# SCH_main.net
KiCad netlist of a schematic drawn in Altium Designer
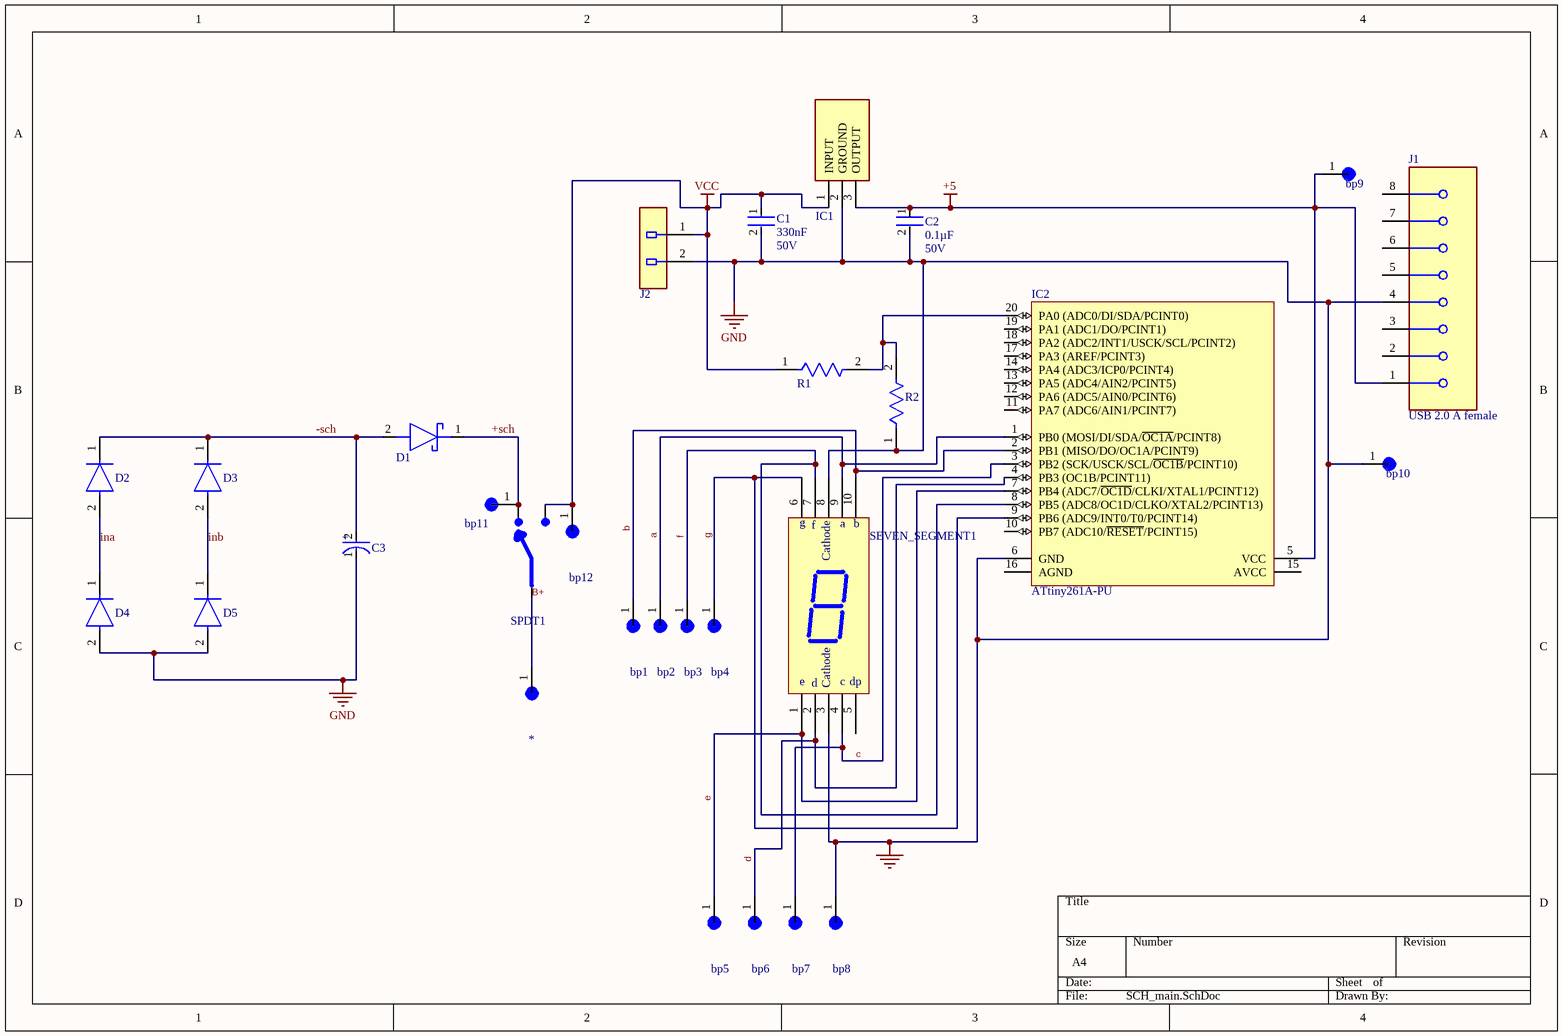
[diagram p0: SCH_main.SchDoc]

(export (version "E")
  (design (tool "Eeschema 10.0.6"))
  (components
    (comp (ref "*")
      (value "Battery Pad")
      (footprint "Battery pad")
      (libsource (lib "Schlib1") (part "Battery Pad"))
    )
    (comp (ref "bp1")
      (value "Battery Pad")
      (footprint "Battery pad")
      (libsource (lib "Schlib1") (part "Battery Pad"))
    )
    (comp (ref "bp2")
      (value "Battery Pad")
      (footprint "Battery pad")
      (libsource (lib "Schlib1") (part "Battery Pad"))
    )
    (comp (ref "bp3")
      (value "Battery Pad")
      (footprint "Battery pad")
      (libsource (lib "Schlib1") (part "Battery Pad"))
    )
    (comp (ref "bp4")
      (value "Battery Pad")
      (footprint "Battery pad")
      (libsource (lib "Schlib1") (part "Battery Pad"))
    )
    (comp (ref "bp5")
      (value "Battery Pad")
      (footprint "Battery pad")
      (libsource (lib "Schlib1") (part "Battery Pad"))
    )
    (comp (ref "bp6")
      (value "Battery Pad")
      (footprint "Battery pad")
      (libsource (lib "Schlib1") (part "Battery Pad"))
    )
    (comp (ref "bp7")
      (value "Battery Pad")
      (footprint "Battery pad")
      (libsource (lib "Schlib1") (part "Battery Pad"))
    )
    (comp (ref "bp8")
      (value "Battery Pad")
      (footprint "Battery pad")
      (libsource (lib "Schlib1") (part "Battery Pad"))
    )
    (comp (ref "bp9")
      (value "Battery Pad")
      (footprint "Battery pad")
      (libsource (lib "Schlib1") (part "Battery Pad"))
    )
    (comp (ref "bp10")
      (value "Battery Pad")
      (footprint "Battery pad")
      (libsource (lib "Schlib1") (part "Battery Pad"))
    )
    (comp (ref "bp11")
      (value "Battery Pad")
      (footprint "Battery pad")
      (libsource (lib "Schlib1") (part "Battery Pad"))
    )
    (comp (ref "bp12")
      (value "Battery Pad")
      (footprint "Battery pad")
      (libsource (lib "Schlib1") (part "Battery Pad"))
    )
    (comp (ref "C1")
      (value "Cap_Kemet_C322C334M5U5TA7301_eec")
      (footprint "Kemet_C322C334M5U5TA7301_0")
      (description "CAP CER 0.33UF 50V Z5U RADIAL")
      (fields
        (field (name "PART NUMBER") "C322C334M5U5TA7301")
        (field (name "MANUFACTURER") "Kemet")
        (field (name "CAPACITANCE") "330nF")
        (field (name "VOLTAGE") "50V")
      )
      (libsource (lib "Integrated_Library1") (part "Cap_Kemet_C322C334M5U5TA7301_eec"))
    )
    (comp (ref "C2")
      (value "Cap_BC_Components_K104Z15Y5VF5TL2_eec")
      (footprint "BC_Components_K104Z15Y5VF5TL2_0")
      (description "CAP CER 0.1UF 50V Y5V RADIAL")
      (fields
        (field (name "MANUFACTURER") "BC Components")
        (field (name "MOUSER PART NUMBER") "594-K104Z15Y5VF5TL2")
        (field (name "CAPACITANCE") "0.1µF")
        (field (name "VOLTAGE") "50V")
      )
      (libsource (lib "Integrated_Library1") (part "Cap_BC_Components_K104Z15Y5VF5TL2_eec"))
    )
    (comp (ref "C3")
      (value "ECA-1CM471")
      (footprint "Panasonic_ECA-1_0")
      (libsource (lib "Schlib1") (part "ECA-1CM471"))
    )
    (comp (ref "D1")
      (value "SD103A-TR")
      (footprint "DIOAD950W60L350D150")
      (description "Schottky Diode")
      (fields (field (name "MOUSER PART NUMBER") "625-SD103A"))
      (libsource (lib "Schlib1") (part "SD103A-TR"))
    )
    (comp (ref "D2")
      (value "Diode_Vishay_1N4007-E3-73_eec")
      (footprint "Vishay_1N4007-E3-73_0")
      (description "DIODE GEN PURP 1KV 1A DO204AL")
      (fields (field (name "PART NUMBER") "1N4007-E3/73") (field (name "MANUFACTURER") "Vishay"))
      (libsource (lib "Integrated_Library1") (part "Diode_Vishay_1N4007-E3-73_eec"))
    )
    (comp (ref "D3")
      (value "Diode_Vishay_1N4007-E3-73_eec")
      (footprint "Vishay_1N4007-E3-73_0")
      (description "DIODE GEN PURP 1KV 1A DO204AL")
      (fields (field (name "PART NUMBER") "1N4007-E3/73") (field (name "MANUFACTURER") "Vishay"))
      (libsource (lib "Integrated_Library1") (part "Diode_Vishay_1N4007-E3-73_eec"))
    )
    (comp (ref "D4")
      (value "Diode_Vishay_1N4007-E3-73_eec")
      (footprint "Vishay_1N4007-E3-73_0")
      (description "DIODE GEN PURP 1KV 1A DO204AL")
      (fields (field (name "PART NUMBER") "1N4007-E3/73") (field (name "MANUFACTURER") "Vishay"))
      (libsource (lib "Integrated_Library1") (part "Diode_Vishay_1N4007-E3-73_eec"))
    )
    (comp (ref "D5")
      (value "Diode_Vishay_1N4007-E3-73_eec")
      (footprint "Vishay_1N4007-E3-73_0")
      (description "DIODE GEN PURP 1KV 1A DO204AL")
      (fields (field (name "PART NUMBER") "1N4007-E3/73") (field (name "MANUFACTURER") "Vishay"))
      (libsource (lib "Integrated_Library1") (part "Diode_Vishay_1N4007-E3-73_eec"))
    )
    (comp (ref "IC1")
      (value "LM7805CT")
      (footprint "TO254P470X1016X2019-3P")
      (description "Integrated Circuit")
      (fields (field (name "MOUSER PART NUMBER") "926-LM7805CT"))
      (libsource (lib "Schlib1") (part "LM7805CT"))
    )
    (comp (ref "IC2")
      (value "ATtiny261A-PU")
      (footprint "20P3")
      (fields (field (name "PARTNUMBER") "ATTINY261A-PU"))
      (libsource (lib "Schlib1") (part "ATTINY261A-PU"))
    )
    (comp (ref "J1")
      (value "USB 2.0 A female")
      (footprint "usbA2F_Molex_67329-8000_0")
      (libsource (lib "Schlib1") (part "67329-8000"))
    )
    (comp (ref "J2")
      (value "826926-2")
      (footprint "TE_826926-2_0")
      (libsource (lib "Integrated_Library1") (part "826926-2"))
    )
    (comp (ref "R1")
      (value "CFR25J100R")
      (footprint "RESISTOR_Tyco_CFR25J100R_0")
      (description "Carbon Film Resistors - Through Hole 100Ohm 1/3W 1200PPM")
      (fields (field (name "MANUFACTURER") "TE Connectivity") (field (name "TOLERANCE") "5%"))
      (libsource (lib "Schlib1") (part "CFR25J100R"))
    )
    (comp (ref "R2")
      (value "CFR25J100R")
      (footprint "RESISTOR_Tyco_CFR25J100R_0")
      (description "Carbon Film Resistors - Through Hole 100Ohm 1/3W 1200PPM")
      (fields (field (name "MANUFACTURER") "TE Connectivity") (field (name "TOLERANCE") "5%"))
      (libsource (lib "Schlib1") (part "CFR25J100R"))
    )
    (comp (ref "SEVEN_SEGMENT1")
      (value "CC_SEVEN_SEGMENT")
      (footprint "7SEG-Avago-Broadcam_HDSP-5551_0")
      (libsource (lib "Schlib1") (part "CC_SEVEN_SEGMENT"))
    )
    (comp (ref "SPDT1")
      (value "spdt_JS202011SCQN")
      (description "C & K COMPONENTS - JS202011SCQN - SWITCH, DPDT, 0.6A, 6VDC, SMD")
      (fields (field (name "MANUFACTURER") "ITT C&K"))
      (libsource (lib "Schlib1") (part "spdt_JS202011SCQN"))
    )
  )
  (nets
    (net (code "1") (name "+5") (class "Default")
      (node (ref "C2") (pin "1") (pinfunction "1_1") (pintype "passive"))
      (node (ref "IC1") (pin "3") (pinfunction "OUTPUT_3") (pintype "passive"))
      (node (ref "IC2") (pin "5") (pinfunction "VCC_5") (pintype "power_in"))
      (node (ref "J1") (pin "1") (pinfunction "1_1") (pintype "passive"))
      (node (ref "bp9") (pin "1") (pinfunction "1_1") (pintype "passive"))
    )
    (net (code "2") (name "/+sch") (class "Default")
      (node (ref "D1") (pin "1") (pinfunction "K_1") (pintype "passive"))
      (node (ref "SPDT1") (pin "2") (pinfunction "2_2") (pintype "passive"))
      (node (ref "bp11") (pin "1") (pinfunction "1_1") (pintype "passive"))
    )
    (net (code "3") (name "/-sch") (class "Default")
      (node (ref "C3") (pin "2") (pinfunction "+_2") (pintype "passive"))
      (node (ref "D1") (pin "2") (pinfunction "A_2") (pintype "passive"))
      (node (ref "D2") (pin "1") (pinfunction "C_1") (pintype "passive"))
      (node (ref "D3") (pin "1") (pinfunction "C_1") (pintype "passive"))
    )
    (net (code "4") (name "/B+") (class "Default")
      (node (ref "*") (pin "1") (pinfunction "1_1") (pintype "passive"))
    )
    (net (code "5") (name "/a") (class "Default")
      (node (ref "IC2") (pin "1") (pinfunction "PB0_(MOSI/DI/SDA/~{OC1A}/PCINT8)_1") (pintype "bidirectional"))
      (node (ref "SEVEN_SEGMENT1") (pin "9") (pinfunction "9_9") (pintype "passive"))
      (node (ref "bp2") (pin "1") (pinfunction "1_1") (pintype "passive"))
    )
    (net (code "6") (name "/b") (class "Default")
      (node (ref "IC2") (pin "2") (pinfunction "PB1_(MISO/DO/OC1A/PCINT9)_2") (pintype "bidirectional"))
      (node (ref "SEVEN_SEGMENT1") (pin "10") (pinfunction "10_10") (pintype "passive"))
      (node (ref "bp1") (pin "1") (pinfunction "1_1") (pintype "passive"))
    )
    (net (code "7") (name "/c") (class "Default")
      (node (ref "IC2") (pin "3") (pinfunction "PB2_(SCK/USCK/SCL/~{OC1B}/PCINT10)_3") (pintype "bidirectional"))
      (node (ref "SEVEN_SEGMENT1") (pin "4") (pinfunction "4_4") (pintype "passive"))
      (node (ref "bp7") (pin "1") (pinfunction "1_1") (pintype "passive"))
    )
    (net (code "8") (name "/d") (class "Default")
      (node (ref "IC2") (pin "4") (pinfunction "PB3_(OC1B/PCINT11)_4") (pintype "bidirectional"))
      (node (ref "SEVEN_SEGMENT1") (pin "2") (pinfunction "2_2") (pintype "passive"))
      (node (ref "bp6") (pin "1") (pinfunction "1_1") (pintype "passive"))
    )
    (net (code "9") (name "/e") (class "Default")
      (node (ref "IC2") (pin "7") (pinfunction "PB4_(ADC7/~{OC1D}/CLKI/XTAL1/PCINT12)_7") (pintype "bidirectional"))
      (node (ref "SEVEN_SEGMENT1") (pin "1") (pinfunction "1_1") (pintype "passive"))
      (node (ref "bp5") (pin "1") (pinfunction "1_1") (pintype "passive"))
    )
    (net (code "10") (name "/f") (class "Default")
      (node (ref "IC2") (pin "8") (pinfunction "PB5_(ADC8/OC1D/CLKO/XTAL2/PCINT13)_8") (pintype "bidirectional"))
      (node (ref "SEVEN_SEGMENT1") (pin "7") (pinfunction "7_7") (pintype "passive"))
      (node (ref "bp3") (pin "1") (pinfunction "1_1") (pintype "passive"))
    )
    (net (code "11") (name "/g") (class "Default")
      (node (ref "IC2") (pin "9") (pinfunction "PB6_(ADC9/INT0/T0/PCINT14)_9") (pintype "bidirectional"))
      (node (ref "SEVEN_SEGMENT1") (pin "6") (pinfunction "6_6") (pintype "passive"))
      (node (ref "bp4") (pin "1") (pinfunction "1_1") (pintype "passive"))
    )
    (net (code "12") (name "/ina") (class "Default")
      (node (ref "D2") (pin "2") (pinfunction "A_2") (pintype "passive"))
      (node (ref "D4") (pin "1") (pinfunction "C_1") (pintype "passive"))
    )
    (net (code "13") (name "/inb") (class "Default")
      (node (ref "D3") (pin "2") (pinfunction "A_2") (pintype "passive"))
      (node (ref "D5") (pin "1") (pinfunction "C_1") (pintype "passive"))
    )
    (net (code "14") (name "GND") (class "Default")
      (node (ref "C1") (pin "2") (pinfunction "2_2") (pintype "passive"))
      (node (ref "C2") (pin "2") (pinfunction "2_2") (pintype "passive"))
      (node (ref "C3") (pin "1") (pinfunction "-_1") (pintype "passive"))
      (node (ref "D4") (pin "2") (pinfunction "A_2") (pintype "passive"))
      (node (ref "D5") (pin "2") (pinfunction "A_2") (pintype "passive"))
      (node (ref "IC1") (pin "2") (pinfunction "GROUND_2") (pintype "passive"))
      (node (ref "IC2") (pin "6") (pinfunction "GND_6") (pintype "power_in"))
      (node (ref "J1") (pin "4") (pinfunction "4_4") (pintype "passive"))
      (node (ref "J2") (pin "2") (pinfunction "2_2") (pintype "passive"))
      (node (ref "R2") (pin "1") (pinfunction "1_1") (pintype "passive"))
      (node (ref "SEVEN_SEGMENT1") (pin "3") (pinfunction "3_3") (pintype "passive"))
      (node (ref "SEVEN_SEGMENT1") (pin "8") (pinfunction "8_8") (pintype "passive"))
      (node (ref "bp10") (pin "1") (pinfunction "1_1") (pintype "passive"))
      (node (ref "bp8") (pin "1") (pinfunction "1_1") (pintype "passive"))
    )
    (net (code "15") (name "Net-(IC2-PA0_(ADC0{slash}DI{slash}SDA{slash}PCINT0))") (class "Default")
      (node (ref "IC2") (pin "20") (pinfunction "PA0_(ADC0/DI/SDA/PCINT0)_20") (pintype "bidirectional"))
      (node (ref "R1") (pin "2") (pinfunction "2_2") (pintype "passive"))
      (node (ref "R2") (pin "2") (pinfunction "2_2") (pintype "passive"))
    )
    (net (code "16") (name "VCC") (class "Default")
      (node (ref "C1") (pin "1") (pinfunction "1_1") (pintype "passive"))
      (node (ref "IC1") (pin "1") (pinfunction "INPUT_1") (pintype "passive"))
      (node (ref "J2") (pin "1") (pinfunction "1_1") (pintype "passive"))
      (node (ref "R1") (pin "1") (pinfunction "1_1") (pintype "passive"))
      (node (ref "SPDT1") (pin "3") (pinfunction "3_3") (pintype "passive"))
      (node (ref "bp12") (pin "1") (pinfunction "1_1") (pintype "passive"))
    )
    (net (code "17") (name "unconnected-(IC2-AGND-Pad16)") (class "Default")
      (node (ref "IC2") (pin "16") (pinfunction "AGND_16") (pintype "power_in"))
    )
    (net (code "18") (name "unconnected-(IC2-AVCC-Pad15)") (class "Default")
      (node (ref "IC2") (pin "15") (pinfunction "AVCC_15") (pintype "power_in"))
    )
    (net (code "19") (name "unconnected-(IC2-PA1_(ADC1{slash}DO{slash}PCINT1)-Pad19)") (class "Default")
      (node (ref "IC2") (pin "19") (pinfunction "PA1_(ADC1/DO/PCINT1)_19") (pintype "bidirectional"))
    )
    (net (code "20") (name "unconnected-(IC2-PA2_(ADC2{slash}INT1{slash}USCK{slash}SCL{slash}PCINT2)-Pad18)") (class "Default")
      (node (ref "IC2") (pin "18") (pinfunction "PA2_(ADC2/INT1/USCK/SCL/PCINT2)_18") (pintype "bidirectional"))
    )
    (net (code "21") (name "unconnected-(IC2-PA3_(AREF{slash}PCINT3)-Pad17)") (class "Default")
      (node (ref "IC2") (pin "17") (pinfunction "PA3_(AREF/PCINT3)_17") (pintype "bidirectional"))
    )
    (net (code "22") (name "unconnected-(IC2-PA4_(ADC3{slash}ICP0{slash}PCINT4)-Pad14)") (class "Default")
      (node (ref "IC2") (pin "14") (pinfunction "PA4_(ADC3/ICP0/PCINT4)_14") (pintype "bidirectional"))
    )
    (net (code "23") (name "unconnected-(IC2-PA5_(ADC4{slash}AIN2{slash}PCINT5)-Pad13)") (class "Default")
      (node (ref "IC2") (pin "13") (pinfunction "PA5_(ADC4/AIN2/PCINT5)_13") (pintype "bidirectional"))
    )
    (net (code "24") (name "unconnected-(IC2-PA6_(ADC5{slash}AIN0{slash}PCINT6)-Pad12)") (class "Default")
      (node (ref "IC2") (pin "12") (pinfunction "PA6_(ADC5/AIN0/PCINT6)_12") (pintype "bidirectional"))
    )
    (net (code "25") (name "unconnected-(IC2-PA7_(ADC6{slash}AIN1{slash}PCINT7)-Pad11)") (class "Default")
      (node (ref "IC2") (pin "11") (pinfunction "PA7_(ADC6/AIN1/PCINT7)_11") (pintype "bidirectional"))
    )
    (net (code "26") (name "unconnected-(IC2-PB7_(ADC10{slash}~{RESET}{slash}PCINT15)-Pad10)") (class "Default")
      (node (ref "IC2") (pin "10") (pinfunction "PB7_(ADC10/~{RESET}/PCINT15)_10") (pintype "bidirectional"))
    )
    (net (code "27") (name "unconnected-(J1-MNT_1-Pad5)") (class "Default")
      (node (ref "J1") (pin "5") (pinfunction "MNT_1_5") (pintype "passive"))
    )
    (net (code "28") (name "unconnected-(J1-MNT_2-Pad6)") (class "Default")
      (node (ref "J1") (pin "6") (pinfunction "MNT_2_6") (pintype "passive"))
    )
    (net (code "29") (name "unconnected-(J1-MNT_3-Pad7)") (class "Default")
      (node (ref "J1") (pin "7") (pinfunction "MNT_3_7") (pintype "passive"))
    )
    (net (code "30") (name "unconnected-(J1-MNT_4-Pad8)") (class "Default")
      (node (ref "J1") (pin "8") (pinfunction "MNT_4_8") (pintype "passive"))
    )
    (net (code "31") (name "unconnected-(J1-Pad2)") (class "Default")
      (node (ref "J1") (pin "2") (pinfunction "2_2") (pintype "passive"))
    )
    (net (code "32") (name "unconnected-(J1-Pad3)") (class "Default")
      (node (ref "J1") (pin "3") (pinfunction "3_3") (pintype "passive"))
    )
    (net (code "33") (name "unconnected-(SEVEN_SEGMENT1-Pad5)") (class "Default")
      (node (ref "SEVEN_SEGMENT1") (pin "5") (pinfunction "5_5") (pintype "passive"))
    )
    (net (code "34") (name "unconnected-(SPDT1-Pad1)") (class "Default")
      (node (ref "SPDT1") (pin "1") (pinfunction "1_1") (pintype "passive"))
    )
  )
)
